# pic32ak_fe.net
KiCad netlist of a schematic drawn in EAGLE
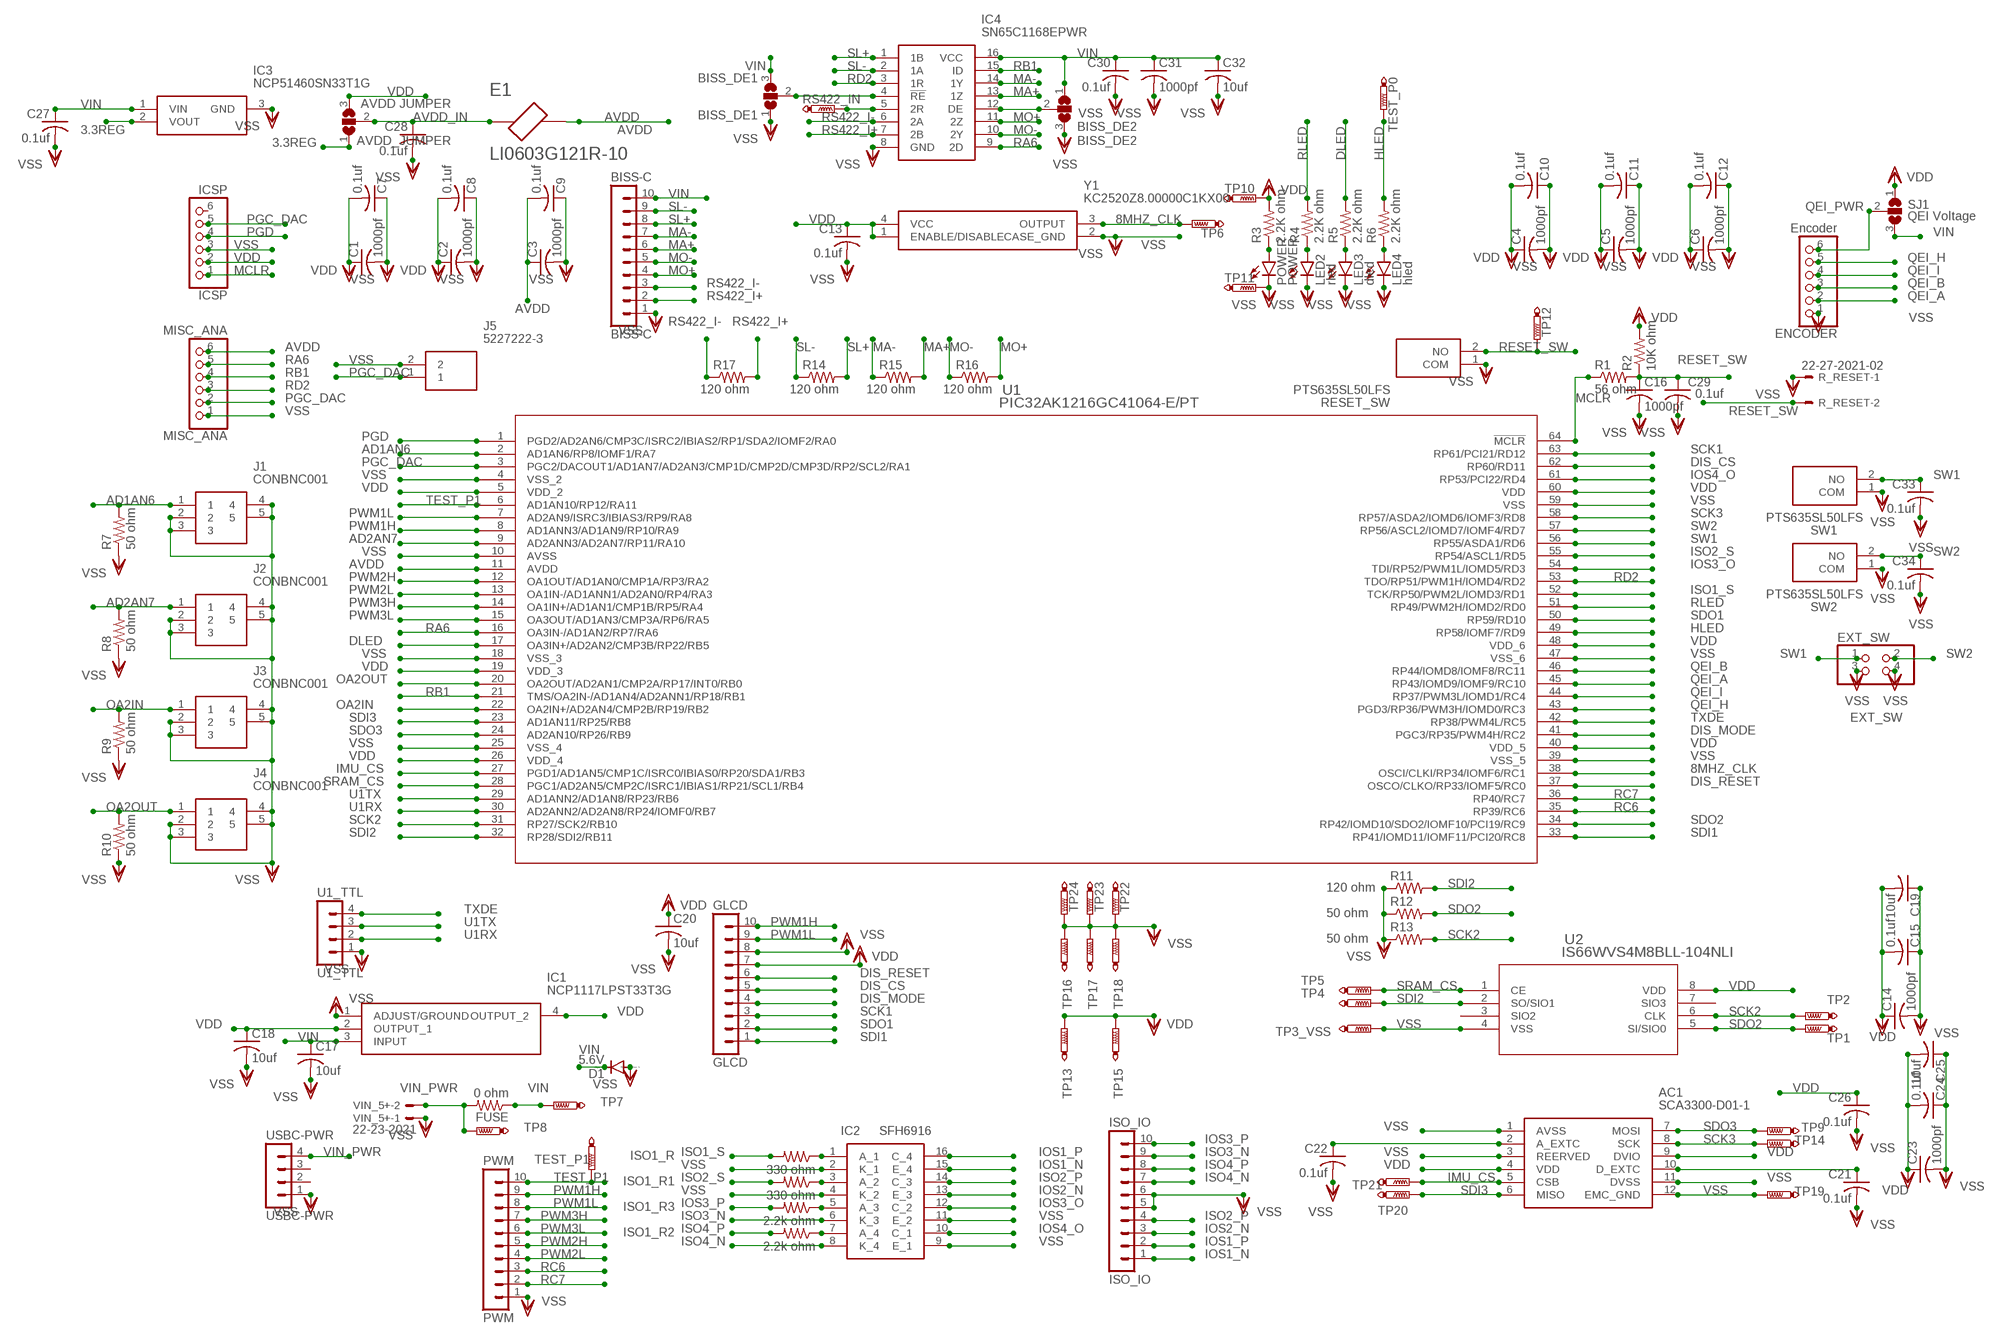
[diagram p0: schematic, sheet 1]

(export (version "E")
  (design (tool "Eeschema 10.0.6"))
  (components
    (comp (ref "AC1")
      (value "SCA3300-D01-1")
      (footprint "eagle-import:SCA3300")
      (fields (field (name "MF") "Murata Electronics"))
      (libsource (lib "eagle-import") (part "SCA3300-D01-1"))
    )
    (comp (ref "AVDD_JUMPER")
      (value "AVDD JUMPER")
      (footprint "eagle-import:SJ_2")
      (libsource (lib "eagle-import") (part "SJ2W"))
    )
    (comp (ref "BISS-C")
      (value "BISS-C")
      (footprint "eagle-import:MA10-1")
      (libsource (lib "eagle-import") (part "MA10-1"))
    )
    (comp (ref "BISS_DE1")
      (value "BISS_DE1")
      (footprint "eagle-import:SJ_2")
      (libsource (lib "eagle-import") (part "SJ2W"))
    )
    (comp (ref "BISS_DE2")
      (value "BISS_DE2")
      (footprint "eagle-import:SJ_2")
      (libsource (lib "eagle-import") (part "SJ2W"))
    )
    (comp (ref "C1")
      (value "1000pf")
      (footprint "eagle-import:C0603")
      (libsource (lib "eagle-import") (part "C-USC0603"))
    )
    (comp (ref "C2")
      (value "1000pf")
      (footprint "eagle-import:C0603")
      (libsource (lib "eagle-import") (part "C-USC0603"))
    )
    (comp (ref "C3")
      (value "1000pf")
      (footprint "eagle-import:C0603")
      (libsource (lib "eagle-import") (part "C-USC0603"))
    )
    (comp (ref "C4")
      (value "1000pf")
      (footprint "eagle-import:C0603")
      (libsource (lib "eagle-import") (part "C-USC0603"))
    )
    (comp (ref "C5")
      (value "1000pf")
      (footprint "eagle-import:C0603")
      (libsource (lib "eagle-import") (part "C-USC0603"))
    )
    (comp (ref "C6")
      (value "1000pf")
      (footprint "eagle-import:C0603")
      (libsource (lib "eagle-import") (part "C-USC0603"))
    )
    (comp (ref "C7")
      (value "0.1uf")
      (footprint "eagle-import:C0603")
      (libsource (lib "eagle-import") (part "C-USC0603"))
    )
    (comp (ref "C8")
      (value "0.1uf")
      (footprint "eagle-import:C0603")
      (libsource (lib "eagle-import") (part "C-USC0603"))
    )
    (comp (ref "C9")
      (value "0.1uf")
      (footprint "eagle-import:C0603")
      (libsource (lib "eagle-import") (part "C-USC0603"))
    )
    (comp (ref "C10")
      (value "0.1uf")
      (footprint "eagle-import:C0603")
      (libsource (lib "eagle-import") (part "C-USC0603"))
    )
    (comp (ref "C11")
      (value "0.1uf")
      (footprint "eagle-import:C0603")
      (libsource (lib "eagle-import") (part "C-USC0603"))
    )
    (comp (ref "C12")
      (value "0.1uf")
      (footprint "eagle-import:C0603")
      (libsource (lib "eagle-import") (part "C-USC0603"))
    )
    (comp (ref "C13")
      (value "0.1uf")
      (footprint "eagle-import:C0603")
      (libsource (lib "eagle-import") (part "C-USC0603"))
    )
    (comp (ref "C14")
      (value "1000pf")
      (footprint "eagle-import:C0603")
      (libsource (lib "eagle-import") (part "C-USC0603"))
    )
    (comp (ref "C15")
      (value "0.1uf")
      (footprint "eagle-import:C0603")
      (libsource (lib "eagle-import") (part "C-USC0603"))
    )
    (comp (ref "C16")
      (value "1000pf")
      (footprint "eagle-import:C0603")
      (libsource (lib "eagle-import") (part "C-USC0603"))
    )
    (comp (ref "C17")
      (value "10uf")
      (footprint "eagle-import:C0805")
      (libsource (lib "eagle-import") (part "C-USC0805"))
    )
    (comp (ref "C18")
      (value "10uf")
      (footprint "eagle-import:C0805")
      (libsource (lib "eagle-import") (part "C-USC0805"))
    )
    (comp (ref "C19")
      (value "10uf")
      (footprint "eagle-import:C0805")
      (libsource (lib "eagle-import") (part "C-USC0805"))
    )
    (comp (ref "C20")
      (value "10uf")
      (footprint "eagle-import:C0805")
      (libsource (lib "eagle-import") (part "C-USC0805"))
    )
    (comp (ref "C21")
      (value "0.1uf")
      (footprint "eagle-import:C0603")
      (libsource (lib "eagle-import") (part "C-USC0603"))
    )
    (comp (ref "C22")
      (value "0.1uf")
      (footprint "eagle-import:C0603")
      (libsource (lib "eagle-import") (part "C-USC0603"))
    )
    (comp (ref "C23")
      (value "1000pf")
      (footprint "eagle-import:C0603")
      (libsource (lib "eagle-import") (part "C-USC0603"))
    )
    (comp (ref "C24")
      (value "0.1uf")
      (footprint "eagle-import:C0603")
      (libsource (lib "eagle-import") (part "C-USC0603"))
    )
    (comp (ref "C25")
      (value "10uf")
      (footprint "eagle-import:C0805")
      (libsource (lib "eagle-import") (part "C-USC0805"))
    )
    (comp (ref "C26")
      (value "0.1uf")
      (footprint "eagle-import:C0603")
      (libsource (lib "eagle-import") (part "C-USC0603"))
    )
    (comp (ref "C27")
      (value "0.1uf")
      (footprint "eagle-import:C0603")
      (libsource (lib "eagle-import") (part "C-USC0603"))
    )
    (comp (ref "C28")
      (value "0.1uf")
      (footprint "eagle-import:C0603")
      (libsource (lib "eagle-import") (part "C-USC0603"))
    )
    (comp (ref "C29")
      (value "0.1uf")
      (footprint "eagle-import:C0603")
      (libsource (lib "eagle-import") (part "C-USC0603"))
    )
    (comp (ref "C30")
      (value "0.1uf")
      (footprint "eagle-import:C0603")
      (libsource (lib "eagle-import") (part "C-USC0603"))
    )
    (comp (ref "C31")
      (value "1000pf")
      (footprint "eagle-import:C0603")
      (libsource (lib "eagle-import") (part "C-USC0603"))
    )
    (comp (ref "C32")
      (value "10uf")
      (footprint "eagle-import:C0805")
      (libsource (lib "eagle-import") (part "C-USC0805"))
    )
    (comp (ref "C33")
      (value "0.1uf")
      (footprint "eagle-import:C0603")
      (libsource (lib "eagle-import") (part "C-USC0603"))
    )
    (comp (ref "C34")
      (value "0.1uf")
      (footprint "eagle-import:C0603")
      (libsource (lib "eagle-import") (part "C-USC0603"))
    )
    (comp (ref "D1")
      (value "5.6V")
      (footprint "eagle-import:SMB")
      (libsource (lib "eagle-import") (part "DIODE-SMB"))
    )
    (comp (ref "E1")
      (value "LI0603G121R-10")
      (footprint "eagle-import:FB_LI0603G121R-10")
      (fields (field (name "MF") "Laird"))
      (libsource (lib "eagle-import") (part "LI0603G121R-10"))
    )
    (comp (ref "ENCODER")
      (value "Encoder")
      (footprint "eagle-import:1X06_90")
      (libsource (lib "eagle-import") (part "PINHD-1X6/90"))
    )
    (comp (ref "EXT_SW")
      (value "EXT_SW")
      (footprint "eagle-import:2X02")
      (libsource (lib "eagle-import") (part "PINHD-2X2"))
    )
    (comp (ref "FUSE")
      (value "0 ohm")
      (footprint "eagle-import:R0805")
      (libsource (lib "eagle-import") (part "R-US_R0805"))
    )
    (comp (ref "GLCD")
      (value "GLCD")
      (footprint "eagle-import:MA10-1")
      (libsource (lib "eagle-import") (part "MA10-1"))
    )
    (comp (ref "IC1")
      (value "NCP1117LPST33T3G")
      (footprint "eagle-import:SOT230P700X180-4N")
      (fields (field (name "MOUSER_PART_NUMBER") "863-NCP1117LPST33T3G"))
      (libsource (lib "eagle-import") (part "NCP1117LPST33T3G"))
    )
    (comp (ref "IC2")
      (value "SFH6916")
      (footprint "eagle-import:SOIC127P700X230-16N")
      (fields (field (name "MOUSER_PART_NUMBER") "782-SFH6916"))
      (libsource (lib "eagle-import") (part "SFH6916"))
    )
    (comp (ref "IC3")
      (value "NCP51460SN33T1G")
      (footprint "eagle-import:SOT96P237X111-3N")
      (fields (field (name "MOUSER_PART_NUMBER") "863-NCP51460SN33T1G"))
      (libsource (lib "eagle-import") (part "NCP51460SN33T1G"))
    )
    (comp (ref "IC4")
      (value "SN65C1168EPWR")
      (footprint "eagle-import:SOP65P640X120-16N")
      (fields (field (name "MOUSER_PART_NUMBER") "595-SN65C1168EPWR"))
      (libsource (lib "eagle-import") (part "SN65C1168EPWR"))
    )
    (comp (ref "ICSP")
      (value "ICSP")
      (footprint "eagle-import:1X06_90")
      (libsource (lib "eagle-import") (part "PINHD-1X6/90"))
    )
    (comp (ref "ISO1_R")
      (value "330 ohm")
      (footprint "eagle-import:R0805")
      (libsource (lib "eagle-import") (part "R-US_R0805"))
    )
    (comp (ref "ISO1_R1")
      (value "330 ohm")
      (footprint "eagle-import:R0805")
      (libsource (lib "eagle-import") (part "R-US_R0805"))
    )
    (comp (ref "ISO1_R2")
      (value "2.2k ohm")
      (footprint "eagle-import:R0805")
      (libsource (lib "eagle-import") (part "R-US_R0805"))
    )
    (comp (ref "ISO1_R3")
      (value "2.2k ohm")
      (footprint "eagle-import:R0805")
      (libsource (lib "eagle-import") (part "R-US_R0805"))
    )
    (comp (ref "ISO_IO")
      (value "ISO_IO")
      (footprint "eagle-import:MA10-1")
      (libsource (lib "eagle-import") (part "MA10-1"))
    )
    (comp (ref "J1")
      (value "CONBNC001")
      (footprint "eagle-import:CONBNC001")
      (fields (field (name "MOUSER_PART_NUMBER") "712-CONBNC001"))
      (libsource (lib "eagle-import") (part "CONBNC001"))
    )
    (comp (ref "J2")
      (value "CONBNC001")
      (footprint "eagle-import:CONBNC001")
      (fields (field (name "MOUSER_PART_NUMBER") "712-CONBNC001"))
      (libsource (lib "eagle-import") (part "CONBNC001"))
    )
    (comp (ref "J3")
      (value "CONBNC001")
      (footprint "eagle-import:CONBNC001")
      (fields (field (name "MOUSER_PART_NUMBER") "712-CONBNC001"))
      (libsource (lib "eagle-import") (part "CONBNC001"))
    )
    (comp (ref "J4")
      (value "CONBNC001")
      (footprint "eagle-import:CONBNC001")
      (fields (field (name "MOUSER_PART_NUMBER") "712-CONBNC001"))
      (libsource (lib "eagle-import") (part "CONBNC001"))
    )
    (comp (ref "J5")
      (value "5227222-3")
      (footprint "eagle-import:52272223")
      (fields (field (name "MOUSER_PART_NUMBER") "571-5227222-3"))
      (libsource (lib "eagle-import") (part "5227222-3"))
    )
    (comp (ref "LED2")
      (value "rled")
      (footprint "eagle-import:CHIP-LED0603")
      (libsource (lib "eagle-import") (part "LEDCHIP-LED0603"))
    )
    (comp (ref "LED3")
      (value "dled")
      (footprint "eagle-import:CHIP-LED0603")
      (libsource (lib "eagle-import") (part "LEDCHIP-LED0603"))
    )
    (comp (ref "LED4")
      (value "hled")
      (footprint "eagle-import:CHIP-LED0603")
      (libsource (lib "eagle-import") (part "LEDCHIP-LED0603"))
    )
    (comp (ref "MISC_ANA")
      (value "MISC_ANA")
      (footprint "eagle-import:1X06_90")
      (libsource (lib "eagle-import") (part "PINHD-1X6/90"))
    )
    (comp (ref "POWER")
      (value "POWER")
      (footprint "eagle-import:CHIP-LED0603")
      (libsource (lib "eagle-import") (part "LEDCHIP-LED0603"))
    )
    (comp (ref "PWM")
      (value "PWM")
      (footprint "eagle-import:MA10-1")
      (libsource (lib "eagle-import") (part "MA10-1"))
    )
    (comp (ref "R1")
      (value "56 ohm")
      (footprint "eagle-import:R0805")
      (libsource (lib "eagle-import") (part "R-US_R0805"))
    )
    (comp (ref "R2")
      (value "10K ohm")
      (footprint "eagle-import:R0805")
      (libsource (lib "eagle-import") (part "R-US_R0805"))
    )
    (comp (ref "R3")
      (value "2.2K ohm")
      (footprint "eagle-import:R0805")
      (libsource (lib "eagle-import") (part "R-US_R0805"))
    )
    (comp (ref "R4")
      (value "2.2K ohm")
      (footprint "eagle-import:R0805")
      (libsource (lib "eagle-import") (part "R-US_R0805"))
    )
    (comp (ref "R5")
      (value "2.2K ohm")
      (footprint "eagle-import:R0805")
      (libsource (lib "eagle-import") (part "R-US_R0805"))
    )
    (comp (ref "R6")
      (value "2.2K ohm")
      (footprint "eagle-import:R0805")
      (libsource (lib "eagle-import") (part "R-US_R0805"))
    )
    (comp (ref "R7")
      (value "50 ohm")
      (footprint "eagle-import:R0805")
      (libsource (lib "eagle-import") (part "R-US_R0805"))
    )
    (comp (ref "R8")
      (value "50 ohm")
      (footprint "eagle-import:R0805")
      (libsource (lib "eagle-import") (part "R-US_R0805"))
    )
    (comp (ref "R9")
      (value "50 ohm")
      (footprint "eagle-import:R0805")
      (libsource (lib "eagle-import") (part "R-US_R0805"))
    )
    (comp (ref "R10")
      (value "50 ohm")
      (footprint "eagle-import:R0805")
      (libsource (lib "eagle-import") (part "R-US_R0805"))
    )
    (comp (ref "R11")
      (value "120 ohm")
      (footprint "eagle-import:R0603")
      (libsource (lib "eagle-import") (part "R-US_R0603"))
    )
    (comp (ref "R12")
      (value "50 ohm")
      (footprint "eagle-import:R0603")
      (libsource (lib "eagle-import") (part "R-US_R0603"))
    )
    (comp (ref "R13")
      (value "50 ohm")
      (footprint "eagle-import:R0603")
      (libsource (lib "eagle-import") (part "R-US_R0603"))
    )
    (comp (ref "R14")
      (value "120 ohm")
      (footprint "eagle-import:R0603")
      (libsource (lib "eagle-import") (part "R-US_R0603"))
    )
    (comp (ref "R15")
      (value "120 ohm")
      (footprint "eagle-import:R0603")
      (libsource (lib "eagle-import") (part "R-US_R0603"))
    )
    (comp (ref "R16")
      (value "120 ohm")
      (footprint "eagle-import:R0603")
      (libsource (lib "eagle-import") (part "R-US_R0603"))
    )
    (comp (ref "R17")
      (value "120 ohm")
      (footprint "eagle-import:R0603")
      (libsource (lib "eagle-import") (part "R-US_R0603"))
    )
    (comp (ref "RESET_SW")
      (value "PTS635SL50LFS")
      (footprint "eagle-import:PTS635SL50LFS")
      (fields (field (name "MOUSER_PART_NUMBER") "611-PTS635SL50LFS"))
      (libsource (lib "eagle-import") (part "PTS635SL50LFS"))
    )
    (comp (ref "RS422_IN")
      (value "PTR1PAD1-13")
      (footprint "eagle-import:P1-13")
      (libsource (lib "eagle-import") (part "PTR1PAD1-13"))
    )
    (comp (ref "R_RESET")
      (value "22-27-2021-02")
      (footprint "eagle-import:6410-02")
      (fields (field (name "MF") "MOLEX"))
      (libsource (lib "eagle-import") (part "22-?-0227-2021"))
    )
    (comp (ref "SJ1")
      (value "QEI Voltage")
      (footprint "eagle-import:SJ_2")
      (libsource (lib "eagle-import") (part "SJ2W"))
    )
    (comp (ref "SW1")
      (value "PTS635SL50LFS")
      (footprint "eagle-import:PTS635SL50LFS")
      (fields (field (name "MOUSER_PART_NUMBER") "611-PTS635SL50LFS"))
      (libsource (lib "eagle-import") (part "PTS635SL50LFS"))
    )
    (comp (ref "SW2")
      (value "PTS635SL50LFS")
      (footprint "eagle-import:PTS635SL50LFS")
      (fields (field (name "MOUSER_PART_NUMBER") "611-PTS635SL50LFS"))
      (libsource (lib "eagle-import") (part "PTS635SL50LFS"))
    )
    (comp (ref "TEST_P0")
      (value "PTR1PAD1-20")
      (footprint "eagle-import:P1-20")
      (libsource (lib "eagle-import") (part "PTR1PAD1-20"))
    )
    (comp (ref "TEST_P1")
      (value "PTR1PAD1-20")
      (footprint "eagle-import:P1-20")
      (libsource (lib "eagle-import") (part "PTR1PAD1-20"))
    )
    (comp (ref "TP1")
      (value "PTR1PAD1-13")
      (footprint "eagle-import:P1-13")
      (libsource (lib "eagle-import") (part "PTR1PAD1-13"))
    )
    (comp (ref "TP2")
      (value "PTR1PAD1-13")
      (footprint "eagle-import:P1-13")
      (libsource (lib "eagle-import") (part "PTR1PAD1-13"))
    )
    (comp (ref "TP3_VSS")
      (value "PTR1PAD1-13")
      (footprint "eagle-import:P1-13")
      (libsource (lib "eagle-import") (part "PTR1PAD1-13"))
    )
    (comp (ref "TP4")
      (value "PTR1PAD1-13")
      (footprint "eagle-import:P1-13")
      (libsource (lib "eagle-import") (part "PTR1PAD1-13"))
    )
    (comp (ref "TP5")
      (value "PTR1PAD1-13")
      (footprint "eagle-import:P1-13")
      (libsource (lib "eagle-import") (part "PTR1PAD1-13"))
    )
    (comp (ref "TP6")
      (value "PTR1PAD1-13")
      (footprint "eagle-import:P1-13")
      (libsource (lib "eagle-import") (part "PTR1PAD1-13"))
    )
    (comp (ref "TP7")
      (value "PTR1PAD1-13")
      (footprint "eagle-import:P1-13")
      (libsource (lib "eagle-import") (part "PTR1PAD1-13"))
    )
    (comp (ref "TP8")
      (value "PTR1PAD1-13")
      (footprint "eagle-import:P1-13")
      (libsource (lib "eagle-import") (part "PTR1PAD1-13"))
    )
    (comp (ref "TP9")
      (value "PTR1PAD1-13")
      (footprint "eagle-import:P1-13")
      (libsource (lib "eagle-import") (part "PTR1PAD1-13"))
    )
    (comp (ref "TP10")
      (value "PTR1PAD1-20")
      (footprint "eagle-import:P1-20")
      (libsource (lib "eagle-import") (part "PTR1PAD1-20"))
    )
    (comp (ref "TP11")
      (value "PTR1PAD1-20")
      (footprint "eagle-import:P1-20")
      (libsource (lib "eagle-import") (part "PTR1PAD1-20"))
    )
    (comp (ref "TP12")
      (value "PTR1PAD1-20")
      (footprint "eagle-import:P1-20")
      (libsource (lib "eagle-import") (part "PTR1PAD1-20"))
    )
    (comp (ref "TP13")
      (value "PTR1PAD1-13")
      (footprint "eagle-import:P1-13")
      (libsource (lib "eagle-import") (part "PTR1PAD1-13"))
    )
    (comp (ref "TP14")
      (value "PTR1PAD1-13")
      (footprint "eagle-import:P1-13")
      (libsource (lib "eagle-import") (part "PTR1PAD1-13"))
    )
    (comp (ref "TP15")
      (value "PTR1PAD1-13")
      (footprint "eagle-import:P1-13")
      (libsource (lib "eagle-import") (part "PTR1PAD1-13"))
    )
    (comp (ref "TP16")
      (value "PTR1PAD1-13")
      (footprint "eagle-import:P1-13")
      (libsource (lib "eagle-import") (part "PTR1PAD1-13"))
    )
    (comp (ref "TP17")
      (value "PTR1PAD1-13")
      (footprint "eagle-import:P1-13")
      (libsource (lib "eagle-import") (part "PTR1PAD1-13"))
    )
    (comp (ref "TP18")
      (value "PTR1PAD1-13")
      (footprint "eagle-import:P1-13")
      (libsource (lib "eagle-import") (part "PTR1PAD1-13"))
    )
    (comp (ref "TP19")
      (value "PTR1PAD1-13")
      (footprint "eagle-import:P1-13")
      (libsource (lib "eagle-import") (part "PTR1PAD1-13"))
    )
    (comp (ref "TP20")
      (value "PTR1PAD1-13")
      (footprint "eagle-import:P1-13")
      (libsource (lib "eagle-import") (part "PTR1PAD1-13"))
    )
    (comp (ref "TP21")
      (value "PTR1PAD1-13")
      (footprint "eagle-import:P1-13")
      (libsource (lib "eagle-import") (part "PTR1PAD1-13"))
    )
    (comp (ref "TP22")
      (value "PTR1PAD1-13")
      (footprint "eagle-import:P1-13")
      (libsource (lib "eagle-import") (part "PTR1PAD1-13"))
    )
    (comp (ref "TP23")
      (value "PTR1PAD1-13")
      (footprint "eagle-import:P1-13")
      (libsource (lib "eagle-import") (part "PTR1PAD1-13"))
    )
    (comp (ref "TP24")
      (value "PTR1PAD1-13")
      (footprint "eagle-import:P1-13")
      (libsource (lib "eagle-import") (part "PTR1PAD1-13"))
    )
    (comp (ref "U1")
      (value "PIC32AK1216GC41064-E/PT")
      (footprint "eagle-import:TQFP64_PT_MCH")
      (fields (field (name "COPYRIGHT") "Copyright (C) 2025 Ultra Librarian. All rights reserved."))
      (libsource (lib "eagle-import") (part "PIC32AK1216GC41064-E/PT"))
    )
    (comp (ref "U1_TTL")
      (value "U1_TTL")
      (footprint "eagle-import:MA04-1")
      (libsource (lib "eagle-import") (part "MA04-1"))
    )
    (comp (ref "U2")
      (value "IS66WVS4M8BLL-104NLI")
      (footprint "eagle-import:SOIC8_150MIL_N_ISI")
      (fields (field (name "COPYRIGHT") "Copyright (C) 2025 Ultra Librarian. All rights reserved."))
      (libsource (lib "eagle-import") (part "IS66WVS4M8BLL-104NLI"))
    )
    (comp (ref "USBC-PWR")
      (value "USBC-PWR")
      (footprint "eagle-import:MA04-1")
      (libsource (lib "eagle-import") (part "MA04-1"))
    )
    (comp (ref "VIN_5+")
      (value "22-23-2021")
      (footprint "eagle-import:22-23-2021")
      (fields (field (name "MF") "MOLEX"))
      (libsource (lib "eagle-import") (part "22-23-2021"))
    )
    (comp (ref "Y1")
      (value "KC2520Z8.00000C1KX00")
      (footprint "eagle-import:KC2520Z800000C1KX00")
      (fields (field (name "MOUSER_PART_NUMBER") "581-KC2520Z800C1KX00"))
      (libsource (lib "eagle-import") (part "KC2520Z8.00000C1KX00"))
    )
  )
  (nets
    (net (code "1") (name "/3.3REG") (class "Default")
      (node (ref "AVDD_JUMPER") (pin "1") (pinfunction "1_1") (pintype "passive"))
      (node (ref "IC3") (pin "2") (pinfunction "VOUT_2") (pintype "output"))
    )
    (net (code "2") (name "/8MHZ_CLK") (class "Default")
      (node (ref "TP6") (pin "TP") (pinfunction "TP_TP") (pintype "input"))
      (node (ref "U1") (pin "38") (pinfunction "OSCI/CLKI/RP34/IOMF6/RC1_38") (pintype "bidirectional"))
      (node (ref "Y1") (pin "3") (pinfunction "OUTPUT_3") (pintype "bidirectional"))
    )
    (net (code "3") (name "/AD1AN6") (class "Default")
      (node (ref "J1") (pin "1") (pinfunction "1_1") (pintype "bidirectional"))
      (node (ref "R7") (pin "2") (pinfunction "2_2") (pintype "passive"))
      (node (ref "U1") (pin "2") (pinfunction "AD1AN6/RP8/IOMF1/RA7_2") (pintype "bidirectional"))
    )
    (net (code "4") (name "/AD2AN7") (class "Default")
      (node (ref "J2") (pin "1") (pinfunction "1_1") (pintype "bidirectional"))
      (node (ref "R8") (pin "2") (pinfunction "2_2") (pintype "passive"))
      (node (ref "U1") (pin "9") (pinfunction "AD2ANN3/AD2AN7/RP11/RA10_9") (pintype "bidirectional"))
    )
    (net (code "5") (name "/AVDD") (class "Default")
      (node (ref "C3") (pin "1") (pinfunction "1_1") (pintype "passive"))
      (node (ref "C9") (pin "2") (pinfunction "2_2") (pintype "passive"))
      (node (ref "E1") (pin "2") (pinfunction "2_2") (pintype "passive"))
      (node (ref "MISC_ANA") (pin "6") (pinfunction "6_6") (pintype "passive"))
      (node (ref "U1") (pin "11") (pinfunction "AVDD_11") (pintype "power_in"))
    )
    (net (code "6") (name "/AVDD_IN") (class "Default")
      (node (ref "AVDD_JUMPER") (pin "2") (pinfunction "2_2") (pintype "passive"))
      (node (ref "C28") (pin "1") (pinfunction "1_1") (pintype "passive"))
      (node (ref "E1") (pin "1") (pinfunction "1_1") (pintype "passive"))
    )
    (net (code "7") (name "/DIS_CS") (class "Default")
      (node (ref "GLCD") (pin "5") (pinfunction "5_5") (pintype "passive"))
      (node (ref "U1") (pin "62") (pinfunction "RP60/RD11_62") (pintype "bidirectional"))
    )
    (net (code "8") (name "/DIS_MODE") (class "Default")
      (node (ref "GLCD") (pin "4") (pinfunction "4_4") (pintype "passive"))
      (node (ref "U1") (pin "41") (pinfunction "PGC3/RP35/PWM4H/RC2_41") (pintype "bidirectional"))
    )
    (net (code "9") (name "/DIS_RESET") (class "Default")
      (node (ref "GLCD") (pin "6") (pinfunction "6_6") (pintype "passive"))
      (node (ref "U1") (pin "37") (pinfunction "OSCO/CLKO/RP33/IOMF5/RC0_37") (pintype "bidirectional"))
    )
    (net (code "10") (name "/DLED") (class "Default")
      (node (ref "R5") (pin "2") (pinfunction "2_2") (pintype "passive"))
      (node (ref "U1") (pin "17") (pinfunction "OA3IN+/AD2AN2/CMP3B/RP22/RB5_17") (pintype "bidirectional"))
    )
    (net (code "11") (name "/HLED") (class "Default")
      (node (ref "R6") (pin "2") (pinfunction "2_2") (pintype "passive"))
      (node (ref "TEST_P0") (pin "TP") (pinfunction "TP_TP") (pintype "input"))
      (node (ref "U1") (pin "49") (pinfunction "RP58/IOMF7/RD9_49") (pintype "bidirectional"))
    )
    (net (code "12") (name "/IMU_CS") (class "Default")
      (node (ref "AC1") (pin "5") (pinfunction "CSB_5") (pintype "bidirectional"))
      (node (ref "TP21") (pin "TP") (pinfunction "TP_TP") (pintype "input"))
      (node (ref "U1") (pin "27") (pinfunction "PGD1/AD1AN5/CMP1C/ISRC0/IBIAS0/RP20/SDA1/RB3_27") (pintype "bidirectional"))
    )
    (net (code "13") (name "/IOS1_N") (class "Default")
      (node (ref "IC2") (pin "15") (pinfunction "E_4_15") (pintype "bidirectional"))
      (node (ref "ISO_IO") (pin "1") (pinfunction "1_1") (pintype "passive"))
    )
    (net (code "14") (name "/IOS1_P") (class "Default")
      (node (ref "IC2") (pin "16") (pinfunction "C_4_16") (pintype "bidirectional"))
      (node (ref "ISO_IO") (pin "2") (pinfunction "2_2") (pintype "passive"))
    )
    (net (code "15") (name "/IOS2_N") (class "Default")
      (node (ref "IC2") (pin "13") (pinfunction "E_3_13") (pintype "bidirectional"))
      (node (ref "ISO_IO") (pin "3") (pinfunction "3_3") (pintype "passive"))
    )
    (net (code "16") (name "/IOS3_O") (class "Default")
      (node (ref "IC2") (pin "12") (pinfunction "C_2_12") (pintype "bidirectional"))
      (node (ref "U1") (pin "54") (pinfunction "TDI/RP52/PWM1L/IOMD5/RD3_54") (pintype "bidirectional"))
    )
    (net (code "17") (name "/IOS3_P") (class "Default")
      (node (ref "ISO1_R3") (pin "2") (pinfunction "2_2") (pintype "passive"))
      (node (ref "ISO_IO") (pin "10") (pinfunction "10_10") (pintype "passive"))
    )
    (net (code "18") (name "/IOS4_O") (class "Default")
      (node (ref "IC2") (pin "10") (pinfunction "C_1_10") (pintype "bidirectional"))
      (node (ref "U1") (pin "61") (pinfunction "RP53/PCI22/RD4_61") (pintype "bidirectional"))
    )
    (net (code "19") (name "/ISO1_S") (class "Default")
      (node (ref "ISO1_R") (pin "2") (pinfunction "2_2") (pintype "passive"))
      (node (ref "U1") (pin "52") (pinfunction "TCK/RP50/PWM2L/IOMD3/RD1_52") (pintype "bidirectional"))
    )
    (net (code "20") (name "/ISO2_P") (class "Default")
      (node (ref "IC2") (pin "14") (pinfunction "C_3_14") (pintype "bidirectional"))
      (node (ref "ISO_IO") (pin "4") (pinfunction "4_4") (pintype "passive"))
    )
    (net (code "21") (name "/ISO2_S") (class "Default")
      (node (ref "ISO1_R1") (pin "2") (pinfunction "2_2") (pintype "passive"))
      (node (ref "U1") (pin "55") (pinfunction "RP54/ASCL1/RD5_55") (pintype "bidirectional"))
    )
    (net (code "22") (name "/ISO3_N") (class "Default")
      (node (ref "IC2") (pin "6") (pinfunction "K_3_6") (pintype "bidirectional"))
      (node (ref "ISO_IO") (pin "9") (pinfunction "9_9") (pintype "passive"))
    )
    (net (code "23") (name "/ISO4_N") (class "Default")
      (node (ref "IC2") (pin "8") (pinfunction "K_4_8") (pintype "bidirectional"))
      (node (ref "ISO_IO") (pin "7") (pinfunction "7_7") (pintype "passive"))
    )
    (net (code "24") (name "/ISO4_P") (class "Default")
      (node (ref "ISO1_R2") (pin "2") (pinfunction "2_2") (pintype "passive"))
      (node (ref "ISO_IO") (pin "8") (pinfunction "8_8") (pintype "passive"))
    )
    (net (code "25") (name "/MA+") (class "Default")
      (node (ref "BISS-C") (pin "6") (pinfunction "6_6") (pintype "passive"))
      (node (ref "IC4") (pin "13") (pinfunction "1Z_13") (pintype "bidirectional"))
      (node (ref "R15") (pin "2") (pinfunction "2_2") (pintype "passive"))
    )
    (net (code "26") (name "/MA-") (class "Default")
      (node (ref "BISS-C") (pin "7") (pinfunction "7_7") (pintype "passive"))
      (node (ref "IC4") (pin "14") (pinfunction "1Y_14") (pintype "bidirectional"))
      (node (ref "R15") (pin "1") (pinfunction "1_1") (pintype "passive"))
    )
    (net (code "27") (name "/MCLR") (class "Default")
      (node (ref "ICSP") (pin "1") (pinfunction "1_1") (pintype "passive"))
      (node (ref "R1") (pin "1") (pinfunction "1_1") (pintype "passive"))
      (node (ref "U1") (pin "64") (pinfunction "~{MCLR}_64") (pintype "input"))
    )
    (net (code "28") (name "/MO+") (class "Default")
      (node (ref "BISS-C") (pin "4") (pinfunction "4_4") (pintype "passive"))
      (node (ref "IC4") (pin "11") (pinfunction "2Z_11") (pintype "bidirectional"))
      (node (ref "R16") (pin "2") (pinfunction "2_2") (pintype "passive"))
    )
    (net (code "29") (name "/MO-") (class "Default")
      (node (ref "BISS-C") (pin "5") (pinfunction "5_5") (pintype "passive"))
      (node (ref "IC4") (pin "10") (pinfunction "2Y_10") (pintype "bidirectional"))
      (node (ref "R16") (pin "1") (pinfunction "1_1") (pintype "passive"))
    )
    (net (code "30") (name "/OA2IN") (class "Default")
      (node (ref "J3") (pin "1") (pinfunction "1_1") (pintype "bidirectional"))
      (node (ref "R9") (pin "2") (pinfunction "2_2") (pintype "passive"))
      (node (ref "U1") (pin "22") (pinfunction "OA2IN+/AD2AN4/CMP2B/RP19/RB2_22") (pintype "bidirectional"))
    )
    (net (code "31") (name "/OA2OUT") (class "Default")
      (node (ref "J4") (pin "1") (pinfunction "1_1") (pintype "bidirectional"))
      (node (ref "R10") (pin "2") (pinfunction "2_2") (pintype "passive"))
      (node (ref "U1") (pin "20") (pinfunction "OA2OUT/AD2AN1/CMP2A/RP17/INT0/RB0_20") (pintype "bidirectional"))
    )
    (net (code "32") (name "/PGC_DAC") (class "Default")
      (node (ref "ICSP") (pin "5") (pinfunction "5_5") (pintype "passive"))
      (node (ref "J5") (pin "1") (pinfunction "1_1") (pintype "bidirectional"))
      (node (ref "MISC_ANA") (pin "2") (pinfunction "2_2") (pintype "passive"))
      (node (ref "U1") (pin "3") (pinfunction "PGC2/DACOUT1/AD1AN7/AD2AN3/CMP1D/CMP2D/CMP3D/RP2/SCL2/RA1_3") (pintype "bidirectional"))
    )
    (net (code "33") (name "/PGD") (class "Default")
      (node (ref "ICSP") (pin "4") (pinfunction "4_4") (pintype "passive"))
      (node (ref "U1") (pin "1") (pinfunction "PGD2/AD2AN6/CMP3C/ISRC2/IBIAS2/RP1/SDA2/IOMF2/RA0_1") (pintype "bidirectional"))
    )
    (net (code "34") (name "/PWM1H") (class "Default")
      (node (ref "GLCD") (pin "10") (pinfunction "10_10") (pintype "passive"))
      (node (ref "PWM") (pin "9") (pinfunction "9_9") (pintype "passive"))
      (node (ref "U1") (pin "8") (pinfunction "AD1ANN3/AD1AN9/RP10/RA9_8") (pintype "bidirectional"))
    )
    (net (code "35") (name "/PWM1L") (class "Default")
      (node (ref "GLCD") (pin "9") (pinfunction "9_9") (pintype "passive"))
      (node (ref "PWM") (pin "8") (pinfunction "8_8") (pintype "passive"))
      (node (ref "U1") (pin "7") (pinfunction "AD2AN9/ISRC3/IBIAS3/RP9/RA8_7") (pintype "bidirectional"))
    )
    (net (code "36") (name "/PWM2H") (class "Default")
      (node (ref "PWM") (pin "5") (pinfunction "5_5") (pintype "passive"))
      (node (ref "U1") (pin "12") (pinfunction "OA1OUT/AD1AN0/CMP1A/RP3/RA2_12") (pintype "bidirectional"))
    )
    (net (code "37") (name "/PWM2L") (class "Default")
      (node (ref "PWM") (pin "4") (pinfunction "4_4") (pintype "passive"))
      (node (ref "U1") (pin "13") (pinfunction "OA1IN-/AD1ANN1/AD2AN0/RP4/RA3_13") (pintype "bidirectional"))
    )
    (net (code "38") (name "/PWM3H") (class "Default")
      (node (ref "PWM") (pin "7") (pinfunction "7_7") (pintype "passive"))
      (node (ref "U1") (pin "14") (pinfunction "OA1IN+/AD1AN1/CMP1B/RP5/RA4_14") (pintype "bidirectional"))
    )
    (net (code "39") (name "/PWM3L") (class "Default")
      (node (ref "PWM") (pin "6") (pinfunction "6_6") (pintype "passive"))
      (node (ref "U1") (pin "15") (pinfunction "OA3OUT/AD1AN3/CMP3A/RP6/RA5_15") (pintype "bidirectional"))
    )
    (net (code "40") (name "/QEI_A") (class "Default")
      (node (ref "ENCODER") (pin "2") (pinfunction "2_2") (pintype "passive"))
      (node (ref "U1") (pin "45") (pinfunction "RP43/IOMD9/IOMF9/RC10_45") (pintype "bidirectional"))
    )
    (net (code "41") (name "/QEI_B") (class "Default")
      (node (ref "ENCODER") (pin "3") (pinfunction "3_3") (pintype "passive"))
      (node (ref "U1") (pin "46") (pinfunction "RP44/IOMD8/IOMF8/RC11_46") (pintype "bidirectional"))
    )
    (net (code "42") (name "/QEI_H") (class "Default")
      (node (ref "ENCODER") (pin "5") (pinfunction "5_5") (pintype "passive"))
      (node (ref "U1") (pin "43") (pinfunction "PGD3/RP36/PWM3H/IOMD0/RC3_43") (pintype "bidirectional"))
    )
    (net (code "43") (name "/QEI_I") (class "Default")
      (node (ref "ENCODER") (pin "4") (pinfunction "4_4") (pintype "passive"))
      (node (ref "U1") (pin "44") (pinfunction "RP37/PWM3L/IOMD1/RC4_44") (pintype "bidirectional"))
    )
    (net (code "44") (name "/QEI_PWR") (class "Default")
      (node (ref "ENCODER") (pin "6") (pinfunction "6_6") (pintype "passive"))
      (node (ref "SJ1") (pin "2") (pinfunction "2_2") (pintype "passive"))
    )
    (net (code "45") (name "/RA6") (class "Default")
      (node (ref "IC4") (pin "9") (pinfunction "2D_9") (pintype "bidirectional"))
      (node (ref "MISC_ANA") (pin "5") (pinfunction "5_5") (pintype "passive"))
      (node (ref "U1") (pin "16") (pinfunction "OA3IN-/AD1AN2/RP7/RA6_16") (pintype "bidirectional"))
    )
    (net (code "46") (name "/RB1") (class "Default")
      (node (ref "IC4") (pin "15") (pinfunction "ID_15") (pintype "bidirectional"))
      (node (ref "MISC_ANA") (pin "4") (pinfunction "4_4") (pintype "passive"))
      (node (ref "U1") (pin "21") (pinfunction "TMS/OA2IN-/AD1AN4/AD2ANN1/RP18/RB1_21") (pintype "bidirectional"))
    )
    (net (code "47") (name "/RC6") (class "Default")
      (node (ref "PWM") (pin "3") (pinfunction "3_3") (pintype "passive"))
      (node (ref "U1") (pin "35") (pinfunction "RP39/RC6_35") (pintype "bidirectional"))
    )
    (net (code "48") (name "/RC7") (class "Default")
      (node (ref "PWM") (pin "2") (pinfunction "2_2") (pintype "passive"))
      (node (ref "U1") (pin "36") (pinfunction "RP40/RC7_36") (pintype "bidirectional"))
    )
    (net (code "49") (name "/RD2") (class "Default")
      (node (ref "IC4") (pin "3") (pinfunction "1R_3") (pintype "bidirectional"))
      (node (ref "MISC_ANA") (pin "3") (pinfunction "3_3") (pintype "passive"))
      (node (ref "U1") (pin "53") (pinfunction "TDO/RP51/PWM1H/IOMD4/RD2_53") (pintype "bidirectional"))
    )
    (net (code "50") (name "/RESET_SW") (class "Default")
      (node (ref "C16") (pin "1") (pinfunction "1_1") (pintype "passive"))
      (node (ref "C29") (pin "1") (pinfunction "1_1") (pintype "passive"))
      (node (ref "R1") (pin "2") (pinfunction "2_2") (pintype "passive"))
      (node (ref "R2") (pin "1") (pinfunction "1_1") (pintype "passive"))
      (node (ref "RESET_SW") (pin "2") (pinfunction "NO_2") (pintype "bidirectional"))
      (node (ref "R_RESET") (pin "2") (pinfunction "S_2") (pintype "passive"))
      (node (ref "TP12") (pin "TP") (pinfunction "TP_TP") (pintype "input"))
    )
    (net (code "51") (name "/RLED") (class "Default")
      (node (ref "R4") (pin "2") (pinfunction "2_2") (pintype "passive"))
      (node (ref "U1") (pin "51") (pinfunction "RP49/PWM2H/IOMD2/RD0_51") (pintype "bidirectional"))
    )
    (net (code "52") (name "/RS422_I+") (class "Default")
      (node (ref "BISS-C") (pin "2") (pinfunction "2_2") (pintype "passive"))
      (node (ref "IC4") (pin "7") (pinfunction "2B_7") (pintype "bidirectional"))
      (node (ref "R17") (pin "2") (pinfunction "2_2") (pintype "passive"))
    )
    (net (code "53") (name "/RS422_I-") (class "Default")
      (node (ref "BISS-C") (pin "3") (pinfunction "3_3") (pintype "passive"))
      (node (ref "IC4") (pin "6") (pinfunction "2A_6") (pintype "bidirectional"))
      (node (ref "R17") (pin "1") (pinfunction "1_1") (pintype "passive"))
    )
    (net (code "54") (name "/SCK1") (class "Default")
      (node (ref "GLCD") (pin "3") (pinfunction "3_3") (pintype "passive"))
      (node (ref "U1") (pin "63") (pinfunction "RP61/PCI21/RD12_63") (pintype "bidirectional"))
    )
    (net (code "55") (name "/SCK2") (class "Default")
      (node (ref "R13") (pin "2") (pinfunction "2_2") (pintype "passive"))
      (node (ref "TP2") (pin "TP") (pinfunction "TP_TP") (pintype "input"))
      (node (ref "U1") (pin "31") (pinfunction "RP27/SCK2/RB10_31") (pintype "bidirectional"))
      (node (ref "U2") (pin "6") (pinfunction "CLK_6") (pintype "input"))
    )
    (net (code "56") (name "/SCK3") (class "Default")
      (node (ref "AC1") (pin "8") (pinfunction "SCK_8") (pintype "bidirectional"))
      (node (ref "TP14") (pin "TP") (pinfunction "TP_TP") (pintype "input"))
      (node (ref "U1") (pin "58") (pinfunction "RP57/ASDA2/IOMD6/IOMF3/RD8_58") (pintype "bidirectional"))
    )
    (net (code "57") (name "/SDI1") (class "Default")
      (node (ref "GLCD") (pin "1") (pinfunction "1_1") (pintype "passive"))
      (node (ref "U1") (pin "33") (pinfunction "RP41/IOMD11/IOMF11/PCI20/RC8_33") (pintype "bidirectional"))
    )
    (net (code "58") (name "/SDI2") (class "Default")
      (node (ref "R11") (pin "2") (pinfunction "2_2") (pintype "passive"))
      (node (ref "TP4") (pin "TP") (pinfunction "TP_TP") (pintype "input"))
      (node (ref "U1") (pin "32") (pinfunction "RP28/SDI2/RB11_32") (pintype "bidirectional"))
      (node (ref "U2") (pin "2") (pinfunction "SO/SIO1_2") (pintype "bidirectional"))
    )
    (net (code "59") (name "/SDI3") (class "Default")
      (node (ref "AC1") (pin "6") (pinfunction "MISO_6") (pintype "bidirectional"))
      (node (ref "TP20") (pin "TP") (pinfunction "TP_TP") (pintype "input"))
      (node (ref "U1") (pin "23") (pinfunction "AD1AN11/RP25/RB8_23") (pintype "bidirectional"))
    )
    (net (code "60") (name "/SDO1") (class "Default")
      (node (ref "GLCD") (pin "2") (pinfunction "2_2") (pintype "passive"))
      (node (ref "U1") (pin "50") (pinfunction "RP59/RD10_50") (pintype "bidirectional"))
    )
    (net (code "61") (name "/SDO2") (class "Default")
      (node (ref "R12") (pin "2") (pinfunction "2_2") (pintype "passive"))
      (node (ref "TP1") (pin "TP") (pinfunction "TP_TP") (pintype "input"))
      (node (ref "U1") (pin "34") (pinfunction "RP42/IOMD10/SDO2/IOMF10/PCI19/RC9_34") (pintype "bidirectional"))
      (node (ref "U2") (pin "5") (pinfunction "SI/SIO0_5") (pintype "bidirectional"))
    )
    (net (code "62") (name "/SDO3") (class "Default")
      (node (ref "AC1") (pin "7") (pinfunction "MOSI_7") (pintype "bidirectional"))
      (node (ref "TP9") (pin "TP") (pinfunction "TP_TP") (pintype "input"))
      (node (ref "U1") (pin "24") (pinfunction "AD2AN10/RP26/RB9_24") (pintype "bidirectional"))
    )
    (net (code "63") (name "/SL+") (class "Default")
      (node (ref "BISS-C") (pin "8") (pinfunction "8_8") (pintype "passive"))
      (node (ref "IC4") (pin "1") (pinfunction "1B_1") (pintype "bidirectional"))
      (node (ref "R14") (pin "2") (pinfunction "2_2") (pintype "passive"))
    )
    (net (code "64") (name "/SL-") (class "Default")
      (node (ref "BISS-C") (pin "9") (pinfunction "9_9") (pintype "passive"))
      (node (ref "IC4") (pin "2") (pinfunction "1A_2") (pintype "bidirectional"))
      (node (ref "R14") (pin "1") (pinfunction "1_1") (pintype "passive"))
    )
    (net (code "65") (name "/SRAM_CS") (class "Default")
      (node (ref "TP5") (pin "TP") (pinfunction "TP_TP") (pintype "input"))
      (node (ref "U1") (pin "28") (pinfunction "PGC1/AD2AN5/CMP2C/ISRC1/IBIAS1/RP21/SCL1/RB4_28") (pintype "bidirectional"))
      (node (ref "U2") (pin "1") (pinfunction "CE_1") (pintype "input"))
    )
    (net (code "66") (name "/SW1") (class "Default")
      (node (ref "C33") (pin "1") (pinfunction "1_1") (pintype "passive"))
      (node (ref "EXT_SW") (pin "1") (pinfunction "1_1") (pintype "passive"))
      (node (ref "SW1") (pin "2") (pinfunction "NO_2") (pintype "bidirectional"))
      (node (ref "U1") (pin "56") (pinfunction "RP55/ASDA1/RD6_56") (pintype "bidirectional"))
    )
    (net (code "67") (name "/SW2") (class "Default")
      (node (ref "C34") (pin "1") (pinfunction "1_1") (pintype "passive"))
      (node (ref "EXT_SW") (pin "2") (pinfunction "2_2") (pintype "passive"))
      (node (ref "SW2") (pin "2") (pinfunction "NO_2") (pintype "bidirectional"))
      (node (ref "U1") (pin "57") (pinfunction "RP56/ASCL2/IOMD7/IOMF4/RD7_57") (pintype "bidirectional"))
    )
    (net (code "68") (name "/TEST_P1") (class "Default")
      (node (ref "PWM") (pin "10") (pinfunction "10_10") (pintype "passive"))
      (node (ref "TEST_P1") (pin "TP") (pinfunction "TP_TP") (pintype "input"))
      (node (ref "U1") (pin "6") (pinfunction "AD1AN10/RP12/RA11_6") (pintype "bidirectional"))
    )
    (net (code "69") (name "/TXDE") (class "Default")
      (node (ref "U1") (pin "42") (pinfunction "RP38/PWM4L/RC5_42") (pintype "bidirectional"))
      (node (ref "U1_TTL") (pin "4") (pinfunction "4_4") (pintype "passive"))
    )
    (net (code "70") (name "/U1RX") (class "Default")
      (node (ref "U1") (pin "30") (pinfunction "AD2ANN2/AD2AN8/RP24/IOMF0/RB7_30") (pintype "bidirectional"))
      (node (ref "U1_TTL") (pin "2") (pinfunction "2_2") (pintype "passive"))
    )
    (net (code "71") (name "/U1TX") (class "Default")
      (node (ref "U1") (pin "29") (pinfunction "AD1ANN2/AD1AN8/RP23/RB6_29") (pintype "bidirectional"))
      (node (ref "U1_TTL") (pin "3") (pinfunction "3_3") (pintype "passive"))
    )
    (net (code "72") (name "/VIN") (class "Default")
      (node (ref "BISS-C") (pin "10") (pinfunction "10_10") (pintype "passive"))
      (node (ref "BISS_DE1") (pin "3") (pinfunction "3_3") (pintype "passive"))
      (node (ref "BISS_DE2") (pin "1") (pinfunction "1_1") (pintype "passive"))
      (node (ref "C17") (pin "1") (pinfunction "1_1") (pintype "passive"))
      (node (ref "C27") (pin "1") (pinfunction "1_1") (pintype "passive"))
      (node (ref "C30") (pin "1") (pinfunction "1_1") (pintype "passive"))
      (node (ref "C31") (pin "1") (pinfunction "1_1") (pintype "passive"))
      (node (ref "C32") (pin "1") (pinfunction "1_1") (pintype "passive"))
      (node (ref "D1") (pin "C") (pinfunction "C_C") (pintype "passive"))
      (node (ref "FUSE") (pin "1") (pinfunction "1_1") (pintype "passive"))
      (node (ref "IC1") (pin "3") (pinfunction "INPUT_3") (pintype "bidirectional"))
      (node (ref "IC3") (pin "1") (pinfunction "VIN_1") (pintype "input"))
      (node (ref "IC4") (pin "16") (pinfunction "VCC_16") (pintype "bidirectional"))
      (node (ref "SJ1") (pin "3") (pinfunction "3_3") (pintype "passive"))
      (node (ref "TP7") (pin "TP") (pinfunction "TP_TP") (pintype "input"))
    )
    (net (code "73") (name "/VIN_PWR") (class "Default")
      (node (ref "FUSE") (pin "2") (pinfunction "2_2") (pintype "passive"))
      (node (ref "TP8") (pin "TP") (pinfunction "TP_TP") (pintype "input"))
      (node (ref "USBC-PWR") (pin "4") (pinfunction "4_4") (pintype "passive"))
      (node (ref "VIN_5+") (pin "2") (pinfunction "S_2") (pintype "passive"))
    )
    (net (code "74") (name "Net-(AC1-A_EXTC)") (class "Default")
      (node (ref "AC1") (pin "2") (pinfunction "A_EXTC_2") (pintype "bidirectional"))
      (node (ref "C22") (pin "1") (pinfunction "1_1") (pintype "passive"))
    )
    (net (code "75") (name "Net-(AC1-D_EXTC)") (class "Default")
      (node (ref "AC1") (pin "10") (pinfunction "D_EXTC_10") (pintype "bidirectional"))
      (node (ref "C21") (pin "1") (pinfunction "1_1") (pintype "passive"))
    )
    (net (code "76") (name "Net-(IC2-A_1)") (class "Default")
      (node (ref "IC2") (pin "1") (pinfunction "A_1_1") (pintype "bidirectional"))
      (node (ref "ISO1_R") (pin "1") (pinfunction "1_1") (pintype "passive"))
    )
    (net (code "77") (name "Net-(IC2-A_2)") (class "Default")
      (node (ref "IC2") (pin "3") (pinfunction "A_2_3") (pintype "bidirectional"))
      (node (ref "ISO1_R1") (pin "1") (pinfunction "1_1") (pintype "passive"))
    )
    (net (code "78") (name "Net-(IC2-A_3)") (class "Default")
      (node (ref "IC2") (pin "5") (pinfunction "A_3_5") (pintype "bidirectional"))
      (node (ref "ISO1_R3") (pin "1") (pinfunction "1_1") (pintype "passive"))
    )
    (net (code "79") (name "Net-(IC2-A_4)") (class "Default")
      (node (ref "IC2") (pin "7") (pinfunction "A_4_7") (pintype "bidirectional"))
      (node (ref "ISO1_R2") (pin "1") (pinfunction "1_1") (pintype "passive"))
    )
    (net (code "80") (name "Net-(IC4-2R)") (class "Default")
      (node (ref "IC4") (pin "5") (pinfunction "2R_5") (pintype "bidirectional"))
      (node (ref "RS422_IN") (pin "TP") (pinfunction "TP_TP") (pintype "input"))
    )
    (net (code "81") (name "Net-(IC4-DE)") (class "Default")
      (node (ref "BISS_DE2") (pin "2") (pinfunction "2_2") (pintype "passive"))
      (node (ref "IC4") (pin "12") (pinfunction "DE_12") (pintype "bidirectional"))
    )
    (net (code "82") (name "Net-(IC4-~{RE})") (class "Default")
      (node (ref "BISS_DE1") (pin "2") (pinfunction "2_2") (pintype "passive"))
      (node (ref "IC4") (pin "4") (pinfunction "~{RE}_4") (pintype "bidirectional"))
    )
    (net (code "83") (name "Net-(LED2-PadA)") (class "Default")
      (node (ref "LED2") (pin "A") (pinfunction "A_A") (pintype "passive"))
      (node (ref "R4") (pin "1") (pinfunction "1_1") (pintype "passive"))
    )
    (net (code "84") (name "Net-(LED3-PadA)") (class "Default")
      (node (ref "LED3") (pin "A") (pinfunction "A_A") (pintype "passive"))
      (node (ref "R5") (pin "1") (pinfunction "1_1") (pintype "passive"))
    )
    (net (code "85") (name "Net-(LED4-PadA)") (class "Default")
      (node (ref "LED4") (pin "A") (pinfunction "A_A") (pintype "passive"))
      (node (ref "R6") (pin "1") (pinfunction "1_1") (pintype "passive"))
    )
    (net (code "86") (name "Net-(POWER-PadA)") (class "Default")
      (node (ref "POWER") (pin "A") (pinfunction "A_A") (pintype "passive"))
      (node (ref "R3") (pin "1") (pinfunction "1_1") (pintype "passive"))
    )
    (net (code "87") (name "VDD") (class "Default")
      (node (ref "AC1") (pin "4") (pinfunction "VDD_4") (pintype "bidirectional"))
      (node (ref "AC1") (pin "9") (pinfunction "DVIO_9") (pintype "bidirectional"))
      (node (ref "AVDD_JUMPER") (pin "3") (pinfunction "3_3") (pintype "passive"))
      (node (ref "C1") (pin "1") (pinfunction "1_1") (pintype "passive"))
      (node (ref "C10") (pin "2") (pinfunction "2_2") (pintype "passive"))
      (node (ref "C11") (pin "2") (pinfunction "2_2") (pintype "passive"))
      (node (ref "C12") (pin "2") (pinfunction "2_2") (pintype "passive"))
      (node (ref "C13") (pin "1") (pinfunction "1_1") (pintype "passive"))
      (node (ref "C14") (pin "1") (pinfunction "1_1") (pintype "passive"))
      (node (ref "C15") (pin "2") (pinfunction "2_2") (pintype "passive"))
      (node (ref "C18") (pin "1") (pinfunction "1_1") (pintype "passive"))
      (node (ref "C19") (pin "2") (pinfunction "2_2") (pintype "passive"))
      (node (ref "C2") (pin "1") (pinfunction "1_1") (pintype "passive"))
      (node (ref "C20") (pin "1") (pinfunction "1_1") (pintype "passive"))
      (node (ref "C23") (pin "1") (pinfunction "1_1") (pintype "passive"))
      (node (ref "C24") (pin "2") (pinfunction "2_2") (pintype "passive"))
      (node (ref "C25") (pin "2") (pinfunction "2_2") (pintype "passive"))
      (node (ref "C26") (pin "1") (pinfunction "1_1") (pintype "passive"))
      (node (ref "C4") (pin "1") (pinfunction "1_1") (pintype "passive"))
      (node (ref "C5") (pin "1") (pinfunction "1_1") (pintype "passive"))
      (node (ref "C6") (pin "1") (pinfunction "1_1") (pintype "passive"))
      (node (ref "C7") (pin "2") (pinfunction "2_2") (pintype "passive"))
      (node (ref "C8") (pin "2") (pinfunction "2_2") (pintype "passive"))
      (node (ref "GLCD") (pin "7") (pinfunction "7_7") (pintype "passive"))
      (node (ref "IC1") (pin "2") (pinfunction "OUTPUT_1_2") (pintype "bidirectional"))
      (node (ref "IC1") (pin "4") (pinfunction "OUTPUT_2_4") (pintype "bidirectional"))
      (node (ref "ICSP") (pin "2") (pinfunction "2_2") (pintype "passive"))
      (node (ref "R2") (pin "2") (pinfunction "2_2") (pintype "passive"))
      (node (ref "R3") (pin "2") (pinfunction "2_2") (pintype "passive"))
      (node (ref "SJ1") (pin "1") (pinfunction "1_1") (pintype "passive"))
      (node (ref "TP10") (pin "TP") (pinfunction "TP_TP") (pintype "input"))
      (node (ref "TP13") (pin "TP") (pinfunction "TP_TP") (pintype "input"))
      (node (ref "TP15") (pin "TP") (pinfunction "TP_TP") (pintype "input"))
      (node (ref "U1") (pin "19") (pinfunction "VDD_3_19") (pintype "power_in"))
      (node (ref "U1") (pin "26") (pinfunction "VDD_4_26") (pintype "power_in"))
      (node (ref "U1") (pin "40") (pinfunction "VDD_5_40") (pintype "power_in"))
      (node (ref "U1") (pin "48") (pinfunction "VDD_6_48") (pintype "power_in"))
      (node (ref "U1") (pin "5") (pinfunction "VDD_2_5") (pintype "power_in"))
      (node (ref "U1") (pin "60") (pinfunction "VDD_60") (pintype "power_in"))
      (node (ref "U2") (pin "8") (pinfunction "VDD_8") (pintype "power_in"))
      (node (ref "Y1") (pin "1") (pinfunction "ENABLE/DISABLE_1") (pintype "bidirectional"))
      (node (ref "Y1") (pin "4") (pinfunction "VCC_4") (pintype "bidirectional"))
    )
    (net (code "88") (name "VSS") (class "Default")
      (node (ref "AC1") (pin "1") (pinfunction "AVSS_1") (pintype "bidirectional"))
      (node (ref "AC1") (pin "11") (pinfunction "DVSS_11") (pintype "bidirectional"))
      (node (ref "AC1") (pin "12") (pinfunction "EMC_GND_12") (pintype "bidirectional"))
      (node (ref "AC1") (pin "3") (pinfunction "REERVED_3") (pintype "bidirectional"))
      (node (ref "BISS-C") (pin "1") (pinfunction "1_1") (pintype "passive"))
      (node (ref "BISS_DE1") (pin "1") (pinfunction "1_1") (pintype "passive"))
      (node (ref "BISS_DE2") (pin "3") (pinfunction "3_3") (pintype "passive"))
      (node (ref "C1") (pin "2") (pinfunction "2_2") (pintype "passive"))
      (node (ref "C10") (pin "1") (pinfunction "1_1") (pintype "passive"))
      (node (ref "C11") (pin "1") (pinfunction "1_1") (pintype "passive"))
      (node (ref "C12") (pin "1") (pinfunction "1_1") (pintype "passive"))
      (node (ref "C13") (pin "2") (pinfunction "2_2") (pintype "passive"))
      (node (ref "C14") (pin "2") (pinfunction "2_2") (pintype "passive"))
      (node (ref "C15") (pin "1") (pinfunction "1_1") (pintype "passive"))
      (node (ref "C16") (pin "2") (pinfunction "2_2") (pintype "passive"))
      (node (ref "C17") (pin "2") (pinfunction "2_2") (pintype "passive"))
      (node (ref "C18") (pin "2") (pinfunction "2_2") (pintype "passive"))
      (node (ref "C19") (pin "1") (pinfunction "1_1") (pintype "passive"))
      (node (ref "C2") (pin "2") (pinfunction "2_2") (pintype "passive"))
      (node (ref "C20") (pin "2") (pinfunction "2_2") (pintype "passive"))
      (node (ref "C21") (pin "2") (pinfunction "2_2") (pintype "passive"))
      (node (ref "C22") (pin "2") (pinfunction "2_2") (pintype "passive"))
      (node (ref "C23") (pin "2") (pinfunction "2_2") (pintype "passive"))
      (node (ref "C24") (pin "1") (pinfunction "1_1") (pintype "passive"))
      (node (ref "C25") (pin "1") (pinfunction "1_1") (pintype "passive"))
      (node (ref "C26") (pin "2") (pinfunction "2_2") (pintype "passive"))
      (node (ref "C27") (pin "2") (pinfunction "2_2") (pintype "passive"))
      (node (ref "C28") (pin "2") (pinfunction "2_2") (pintype "passive"))
      (node (ref "C29") (pin "2") (pinfunction "2_2") (pintype "passive"))
      (node (ref "C3") (pin "2") (pinfunction "2_2") (pintype "passive"))
      (node (ref "C30") (pin "2") (pinfunction "2_2") (pintype "passive"))
      (node (ref "C31") (pin "2") (pinfunction "2_2") (pintype "passive"))
      (node (ref "C32") (pin "2") (pinfunction "2_2") (pintype "passive"))
      (node (ref "C33") (pin "2") (pinfunction "2_2") (pintype "passive"))
      (node (ref "C34") (pin "2") (pinfunction "2_2") (pintype "passive"))
      (node (ref "C4") (pin "2") (pinfunction "2_2") (pintype "passive"))
      (node (ref "C5") (pin "2") (pinfunction "2_2") (pintype "passive"))
      (node (ref "C6") (pin "2") (pinfunction "2_2") (pintype "passive"))
      (node (ref "C7") (pin "1") (pinfunction "1_1") (pintype "passive"))
      (node (ref "C8") (pin "1") (pinfunction "1_1") (pintype "passive"))
      (node (ref "C9") (pin "1") (pinfunction "1_1") (pintype "passive"))
      (node (ref "D1") (pin "A") (pinfunction "A_A") (pintype "passive"))
      (node (ref "ENCODER") (pin "1") (pinfunction "1_1") (pintype "passive"))
      (node (ref "EXT_SW") (pin "3") (pinfunction "3_3") (pintype "passive"))
      (node (ref "EXT_SW") (pin "4") (pinfunction "4_4") (pintype "passive"))
      (node (ref "GLCD") (pin "8") (pinfunction "8_8") (pintype "passive"))
      (node (ref "IC1") (pin "1") (pinfunction "ADJUST/GROUND_1") (pintype "bidirectional"))
      (node (ref "IC2") (pin "11") (pinfunction "E_2_11") (pintype "bidirectional"))
      (node (ref "IC2") (pin "2") (pinfunction "K_1_2") (pintype "bidirectional"))
      (node (ref "IC2") (pin "4") (pinfunction "K_2_4") (pintype "bidirectional"))
      (node (ref "IC2") (pin "9") (pinfunction "E_1_9") (pintype "bidirectional"))
      (node (ref "IC3") (pin "3") (pinfunction "GND_3") (pintype "power_in"))
      (node (ref "IC4") (pin "8") (pinfunction "GND_8") (pintype "bidirectional"))
      (node (ref "ICSP") (pin "3") (pinfunction "3_3") (pintype "passive"))
      (node (ref "ISO_IO") (pin "5") (pinfunction "5_5") (pintype "passive"))
      (node (ref "ISO_IO") (pin "6") (pinfunction "6_6") (pintype "passive"))
      (node (ref "J1") (pin "2") (pinfunction "2_2") (pintype "bidirectional"))
      (node (ref "J1") (pin "3") (pinfunction "3_3") (pintype "bidirectional"))
      (node (ref "J1") (pin "4") (pinfunction "4_4") (pintype "bidirectional"))
      (node (ref "J1") (pin "5") (pinfunction "5_5") (pintype "bidirectional"))
      (node (ref "J2") (pin "2") (pinfunction "2_2") (pintype "bidirectional"))
      (node (ref "J2") (pin "3") (pinfunction "3_3") (pintype "bidirectional"))
      (node (ref "J2") (pin "4") (pinfunction "4_4") (pintype "bidirectional"))
      (node (ref "J2") (pin "5") (pinfunction "5_5") (pintype "bidirectional"))
      (node (ref "J3") (pin "2") (pinfunction "2_2") (pintype "bidirectional"))
      (node (ref "J3") (pin "3") (pinfunction "3_3") (pintype "bidirectional"))
      (node (ref "J3") (pin "4") (pinfunction "4_4") (pintype "bidirectional"))
      (node (ref "J3") (pin "5") (pinfunction "5_5") (pintype "bidirectional"))
      (node (ref "J4") (pin "2") (pinfunction "2_2") (pintype "bidirectional"))
      (node (ref "J4") (pin "3") (pinfunction "3_3") (pintype "bidirectional"))
      (node (ref "J4") (pin "4") (pinfunction "4_4") (pintype "bidirectional"))
      (node (ref "J4") (pin "5") (pinfunction "5_5") (pintype "bidirectional"))
      (node (ref "J5") (pin "2") (pinfunction "2_2") (pintype "bidirectional"))
      (node (ref "LED2") (pin "C") (pinfunction "C_C") (pintype "passive"))
      (node (ref "LED3") (pin "C") (pinfunction "C_C") (pintype "passive"))
      (node (ref "LED4") (pin "C") (pinfunction "C_C") (pintype "passive"))
      (node (ref "MISC_ANA") (pin "1") (pinfunction "1_1") (pintype "passive"))
      (node (ref "POWER") (pin "C") (pinfunction "C_C") (pintype "passive"))
      (node (ref "PWM") (pin "1") (pinfunction "1_1") (pintype "passive"))
      (node (ref "R10") (pin "1") (pinfunction "1_1") (pintype "passive"))
      (node (ref "R11") (pin "1") (pinfunction "1_1") (pintype "passive"))
      (node (ref "R12") (pin "1") (pinfunction "1_1") (pintype "passive"))
      (node (ref "R13") (pin "1") (pinfunction "1_1") (pintype "passive"))
      (node (ref "R7") (pin "1") (pinfunction "1_1") (pintype "passive"))
      (node (ref "R8") (pin "1") (pinfunction "1_1") (pintype "passive"))
      (node (ref "R9") (pin "1") (pinfunction "1_1") (pintype "passive"))
      (node (ref "RESET_SW") (pin "1") (pinfunction "COM_1") (pintype "bidirectional"))
      (node (ref "R_RESET") (pin "1") (pinfunction "S_1") (pintype "passive"))
      (node (ref "SW1") (pin "1") (pinfunction "COM_1") (pintype "bidirectional"))
      (node (ref "SW2") (pin "1") (pinfunction "COM_1") (pintype "bidirectional"))
      (node (ref "TP11") (pin "TP") (pinfunction "TP_TP") (pintype "input"))
      (node (ref "TP16") (pin "TP") (pinfunction "TP_TP") (pintype "input"))
      (node (ref "TP17") (pin "TP") (pinfunction "TP_TP") (pintype "input"))
      (node (ref "TP18") (pin "TP") (pinfunction "TP_TP") (pintype "input"))
      (node (ref "TP19") (pin "TP") (pinfunction "TP_TP") (pintype "input"))
      (node (ref "TP22") (pin "TP") (pinfunction "TP_TP") (pintype "input"))
      (node (ref "TP23") (pin "TP") (pinfunction "TP_TP") (pintype "input"))
      (node (ref "TP24") (pin "TP") (pinfunction "TP_TP") (pintype "input"))
      (node (ref "TP3_VSS") (pin "TP") (pinfunction "TP_TP") (pintype "input"))
      (node (ref "U1") (pin "10") (pinfunction "AVSS_10") (pintype "passive"))
      (node (ref "U1") (pin "18") (pinfunction "VSS_3_18") (pintype "passive"))
      (node (ref "U1") (pin "25") (pinfunction "VSS_4_25") (pintype "passive"))
      (node (ref "U1") (pin "39") (pinfunction "VSS_5_39") (pintype "passive"))
      (node (ref "U1") (pin "4") (pinfunction "VSS_2_4") (pintype "passive"))
      (node (ref "U1") (pin "47") (pinfunction "VSS_6_47") (pintype "passive"))
      (node (ref "U1") (pin "59") (pinfunction "VSS_59") (pintype "passive"))
      (node (ref "U1_TTL") (pin "1") (pinfunction "1_1") (pintype "passive"))
      (node (ref "U2") (pin "4") (pinfunction "VSS_4") (pintype "passive"))
      (node (ref "USBC-PWR") (pin "1") (pinfunction "1_1") (pintype "passive"))
      (node (ref "VIN_5+") (pin "1") (pinfunction "S_1") (pintype "passive"))
      (node (ref "Y1") (pin "2") (pinfunction "CASE_GND_2") (pintype "bidirectional"))
    )
    (net (code "89") (name "unconnected-(ICSP-Pad6)") (class "Default")
      (node (ref "ICSP") (pin "6") (pinfunction "6_6") (pintype "passive"))
    )
    (net (code "90") (name "unconnected-(U2-SIO2-Pad3)") (class "Default")
      (node (ref "U2") (pin "3") (pinfunction "SIO2_3") (pintype "bidirectional"))
    )
    (net (code "91") (name "unconnected-(U2-SIO3-Pad7)") (class "Default")
      (node (ref "U2") (pin "7") (pinfunction "SIO3_7") (pintype "bidirectional"))
    )
    (net (code "92") (name "unconnected-(USBC-PWR-Pad2)") (class "Default")
      (node (ref "USBC-PWR") (pin "2") (pinfunction "2_2") (pintype "passive"))
    )
    (net (code "93") (name "unconnected-(USBC-PWR-Pad3)") (class "Default")
      (node (ref "USBC-PWR") (pin "3") (pinfunction "3_3") (pintype "passive"))
    )
  )
)
